# 16_ch_sample-and-hold_card_-_single-side.net
KiCad netlist of a schematic drawn in EAGLE
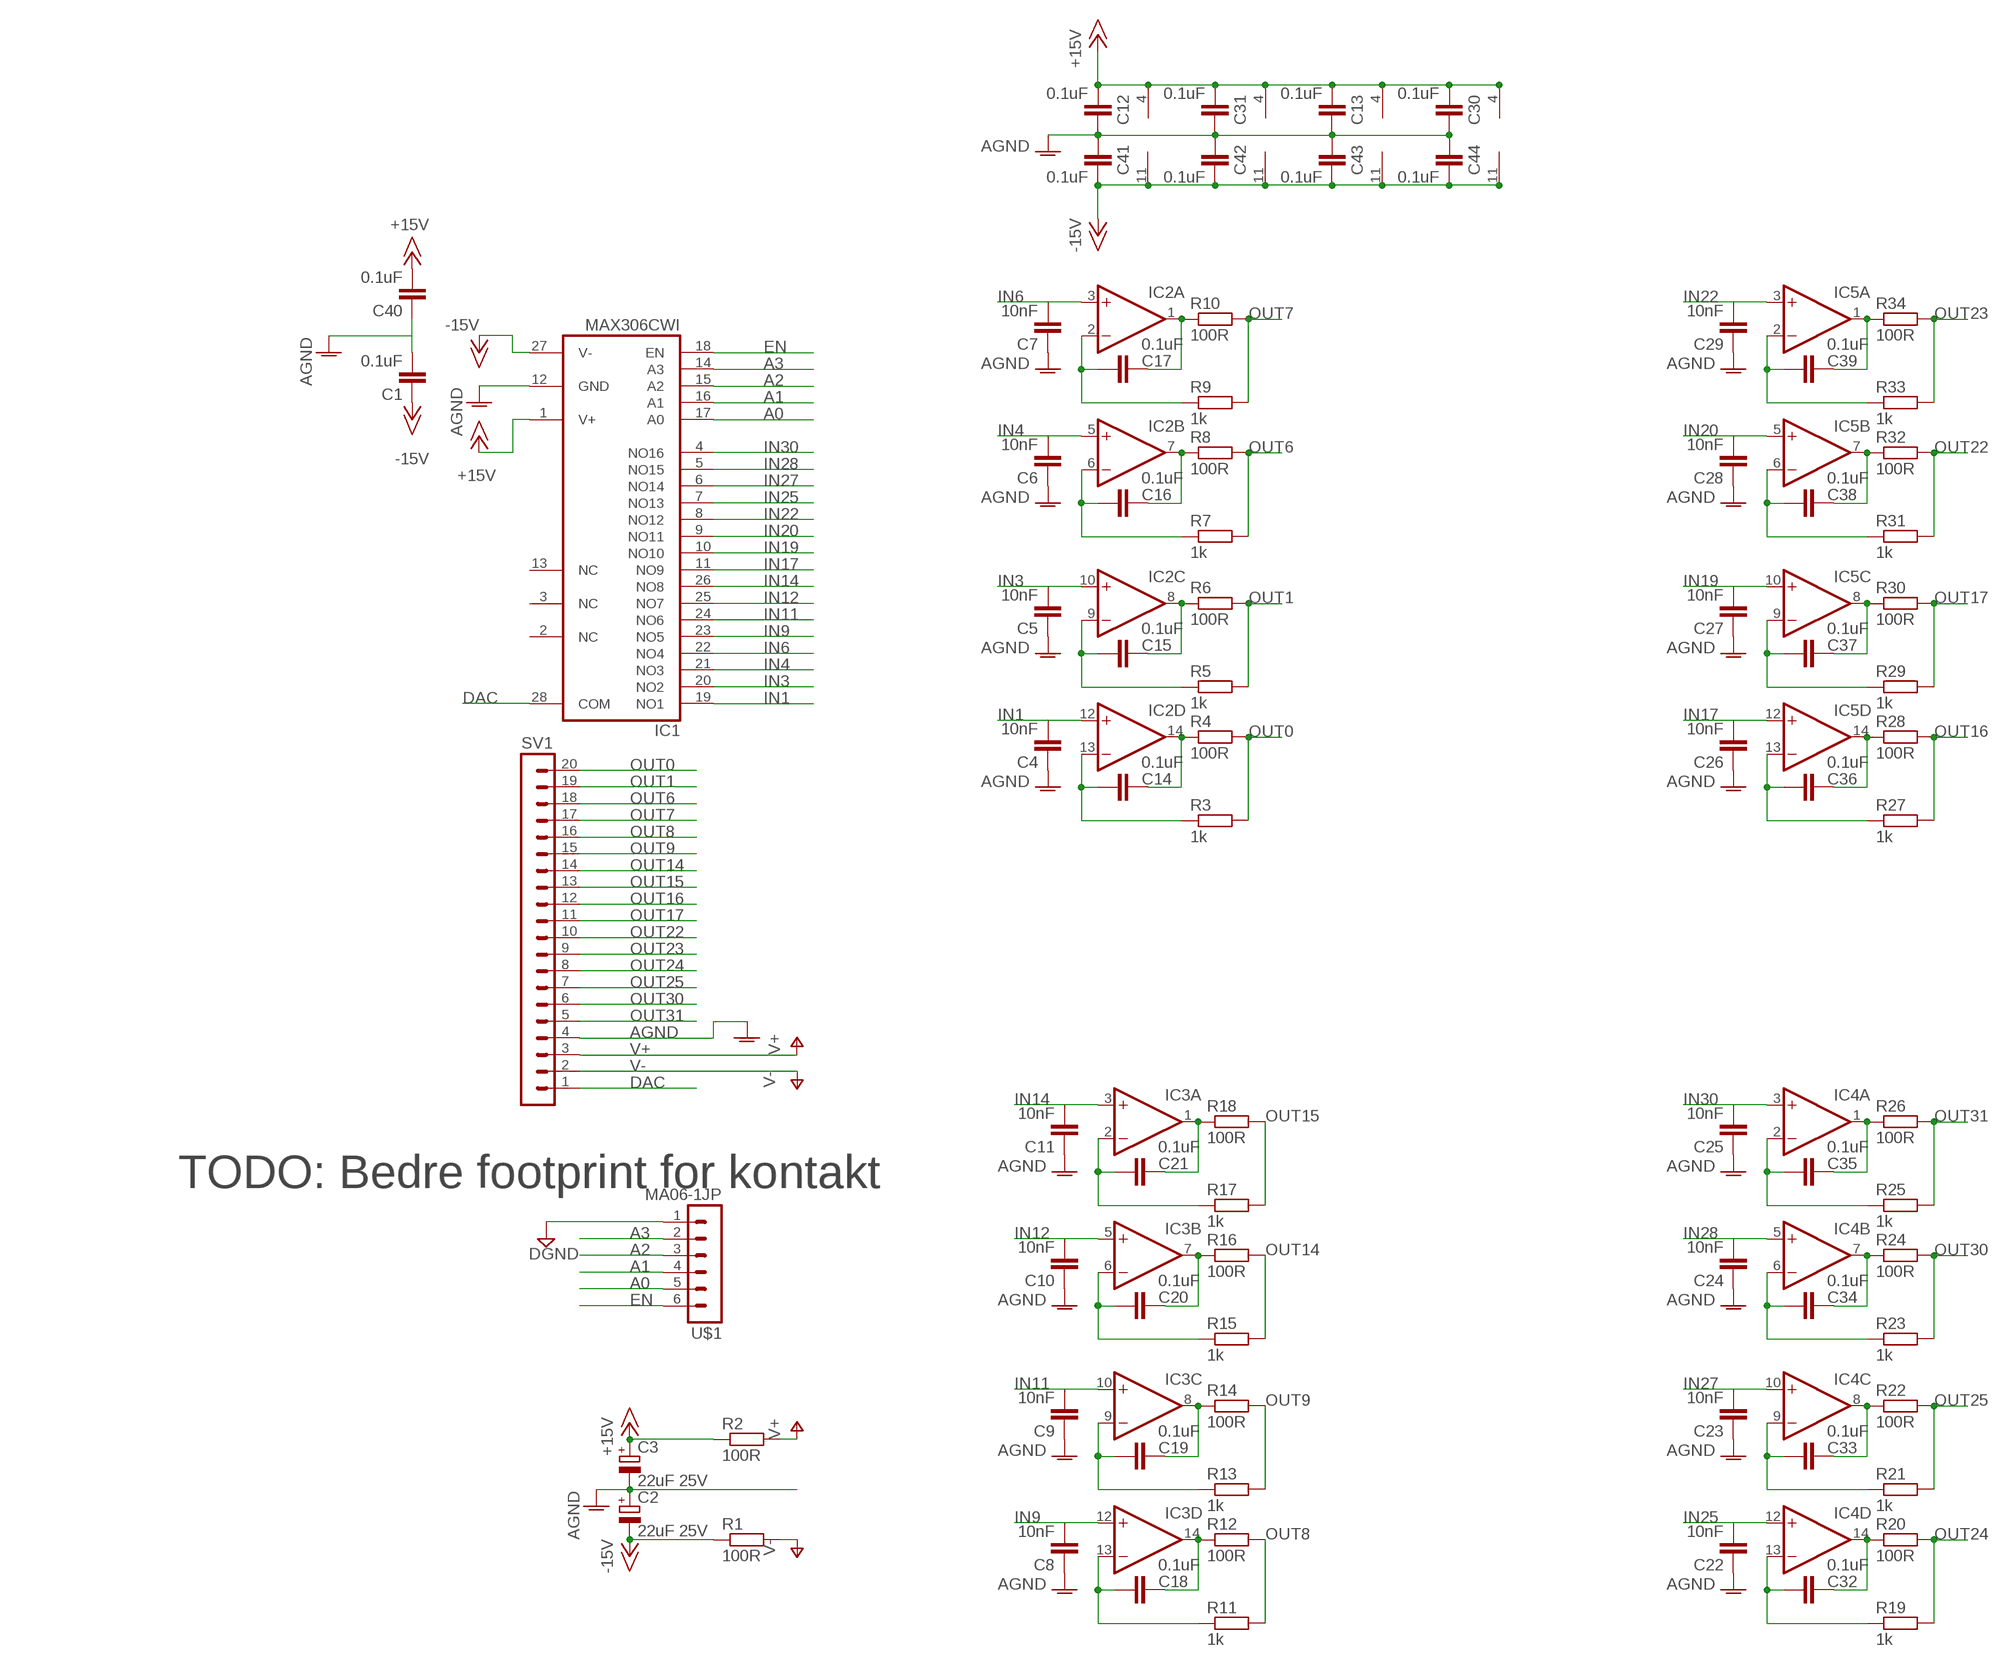
[diagram p0: schematic, sheet 1]

(export (version "E")
  (design (tool "Eeschema 10.0.6"))
  (components
    (comp (ref "C1")
      (value "0.1uF")
      (footprint "eagle-import:C0603")
      (libsource (lib "eagle-import") (part "C-EUC0603"))
    )
    (comp (ref "C2")
      (value "22uF 25V")
      (footprint "eagle-import:E2,5-5")
      (libsource (lib "eagle-import") (part "CPOL-EUE2.5-5"))
    )
    (comp (ref "C3")
      (value "22uF 25V")
      (footprint "eagle-import:E2,5-5")
      (libsource (lib "eagle-import") (part "CPOL-EUE2.5-5"))
    )
    (comp (ref "C4")
      (value "10nF")
      (footprint "eagle-import:C1206")
      (libsource (lib "eagle-import") (part "C-EUC1206"))
    )
    (comp (ref "C5")
      (value "10nF")
      (footprint "eagle-import:C1206")
      (libsource (lib "eagle-import") (part "C-EUC1206"))
    )
    (comp (ref "C6")
      (value "10nF")
      (footprint "eagle-import:C1206")
      (libsource (lib "eagle-import") (part "C-EUC1206"))
    )
    (comp (ref "C7")
      (value "10nF")
      (footprint "eagle-import:C1206")
      (libsource (lib "eagle-import") (part "C-EUC1206"))
    )
    (comp (ref "C8")
      (value "10nF")
      (footprint "eagle-import:C1206")
      (libsource (lib "eagle-import") (part "C-EUC1206"))
    )
    (comp (ref "C9")
      (value "10nF")
      (footprint "eagle-import:C1206")
      (libsource (lib "eagle-import") (part "C-EUC1206"))
    )
    (comp (ref "C10")
      (value "10nF")
      (footprint "eagle-import:C1206")
      (libsource (lib "eagle-import") (part "C-EUC1206"))
    )
    (comp (ref "C11")
      (value "10nF")
      (footprint "eagle-import:C1206")
      (libsource (lib "eagle-import") (part "C-EUC1206"))
    )
    (comp (ref "C12")
      (value "0.1uF")
      (footprint "eagle-import:C0603")
      (libsource (lib "eagle-import") (part "C-EUC0603"))
    )
    (comp (ref "C13")
      (value "0.1uF")
      (footprint "eagle-import:C0603")
      (libsource (lib "eagle-import") (part "C-EUC0603"))
    )
    (comp (ref "C14")
      (value "0.1uF")
      (footprint "eagle-import:C0603")
      (libsource (lib "eagle-import") (part "C-EUC0603"))
    )
    (comp (ref "C15")
      (value "0.1uF")
      (footprint "eagle-import:C0603")
      (libsource (lib "eagle-import") (part "C-EUC0603"))
    )
    (comp (ref "C16")
      (value "0.1uF")
      (footprint "eagle-import:C0603")
      (libsource (lib "eagle-import") (part "C-EUC0603"))
    )
    (comp (ref "C17")
      (value "0.1uF")
      (footprint "eagle-import:C0603")
      (libsource (lib "eagle-import") (part "C-EUC0603"))
    )
    (comp (ref "C18")
      (value "0.1uF")
      (footprint "eagle-import:C0603")
      (libsource (lib "eagle-import") (part "C-EUC0603"))
    )
    (comp (ref "C19")
      (value "0.1uF")
      (footprint "eagle-import:C0603")
      (libsource (lib "eagle-import") (part "C-EUC0603"))
    )
    (comp (ref "C20")
      (value "0.1uF")
      (footprint "eagle-import:C0603")
      (libsource (lib "eagle-import") (part "C-EUC0603"))
    )
    (comp (ref "C21")
      (value "0.1uF")
      (footprint "eagle-import:C0603")
      (libsource (lib "eagle-import") (part "C-EUC0603"))
    )
    (comp (ref "C22")
      (value "10nF")
      (footprint "eagle-import:C1206")
      (libsource (lib "eagle-import") (part "C-EUC1206"))
    )
    (comp (ref "C23")
      (value "10nF")
      (footprint "eagle-import:C1206")
      (libsource (lib "eagle-import") (part "C-EUC1206"))
    )
    (comp (ref "C24")
      (value "10nF")
      (footprint "eagle-import:C1206")
      (libsource (lib "eagle-import") (part "C-EUC1206"))
    )
    (comp (ref "C25")
      (value "10nF")
      (footprint "eagle-import:C1206")
      (libsource (lib "eagle-import") (part "C-EUC1206"))
    )
    (comp (ref "C26")
      (value "10nF")
      (footprint "eagle-import:C1206")
      (libsource (lib "eagle-import") (part "C-EUC1206"))
    )
    (comp (ref "C27")
      (value "10nF")
      (footprint "eagle-import:C1206")
      (libsource (lib "eagle-import") (part "C-EUC1206"))
    )
    (comp (ref "C28")
      (value "10nF")
      (footprint "eagle-import:C1206")
      (libsource (lib "eagle-import") (part "C-EUC1206"))
    )
    (comp (ref "C29")
      (value "10nF")
      (footprint "eagle-import:C1206")
      (libsource (lib "eagle-import") (part "C-EUC1206"))
    )
    (comp (ref "C30")
      (value "0.1uF")
      (footprint "eagle-import:C0603")
      (libsource (lib "eagle-import") (part "C-EUC0603"))
    )
    (comp (ref "C31")
      (value "0.1uF")
      (footprint "eagle-import:C0603")
      (libsource (lib "eagle-import") (part "C-EUC0603"))
    )
    (comp (ref "C32")
      (value "0.1uF")
      (footprint "eagle-import:C0603")
      (libsource (lib "eagle-import") (part "C-EUC0603"))
    )
    (comp (ref "C33")
      (value "0.1uF")
      (footprint "eagle-import:C0603")
      (libsource (lib "eagle-import") (part "C-EUC0603"))
    )
    (comp (ref "C34")
      (value "0.1uF")
      (footprint "eagle-import:C0603")
      (libsource (lib "eagle-import") (part "C-EUC0603"))
    )
    (comp (ref "C35")
      (value "0.1uF")
      (footprint "eagle-import:C0603")
      (libsource (lib "eagle-import") (part "C-EUC0603"))
    )
    (comp (ref "C36")
      (value "0.1uF")
      (footprint "eagle-import:C0603")
      (libsource (lib "eagle-import") (part "C-EUC0603"))
    )
    (comp (ref "C37")
      (value "0.1uF")
      (footprint "eagle-import:C0603")
      (libsource (lib "eagle-import") (part "C-EUC0603"))
    )
    (comp (ref "C38")
      (value "0.1uF")
      (footprint "eagle-import:C0603")
      (libsource (lib "eagle-import") (part "C-EUC0603"))
    )
    (comp (ref "C39")
      (value "0.1uF")
      (footprint "eagle-import:C0603")
      (libsource (lib "eagle-import") (part "C-EUC0603"))
    )
    (comp (ref "C40")
      (value "0.1uF")
      (footprint "eagle-import:C0603")
      (libsource (lib "eagle-import") (part "C-EUC0603"))
    )
    (comp (ref "C41")
      (value "0.1uF")
      (footprint "eagle-import:C0603")
      (libsource (lib "eagle-import") (part "C-EUC0603"))
    )
    (comp (ref "C42")
      (value "0.1uF")
      (footprint "eagle-import:C0603")
      (libsource (lib "eagle-import") (part "C-EUC0603"))
    )
    (comp (ref "C43")
      (value "0.1uF")
      (footprint "eagle-import:C0603")
      (libsource (lib "eagle-import") (part "C-EUC0603"))
    )
    (comp (ref "C44")
      (value "0.1uF")
      (footprint "eagle-import:C0603")
      (libsource (lib "eagle-import") (part "C-EUC0603"))
    )
    (comp (ref "IC1")
      (value "MAX306CWI")
      (footprint "eagle-import:SO28L")
      (fields (field (name "MF") "MAXIM"))
      (libsource (lib "eagle-import") (part "MAX306CWI"))
    )
    (comp (ref "IC2")
      (value "TL074D")
      (footprint "eagle-import:SO14")
      (libsource (lib "eagle-import") (part "TL074D"))
    )
    (comp (ref "IC3")
      (value "TL074D")
      (footprint "eagle-import:SO14")
      (libsource (lib "eagle-import") (part "TL074D"))
    )
    (comp (ref "IC4")
      (value "TL074D")
      (footprint "eagle-import:SO14")
      (libsource (lib "eagle-import") (part "TL074D"))
    )
    (comp (ref "IC5")
      (value "TL074D")
      (footprint "eagle-import:SO14")
      (libsource (lib "eagle-import") (part "TL074D"))
    )
    (comp (ref "R1")
      (value "100R")
      (footprint "eagle-import:0207_7")
      (libsource (lib "eagle-import") (part "R-EU_0207/7"))
    )
    (comp (ref "R2")
      (value "100R")
      (footprint "eagle-import:0207_7")
      (libsource (lib "eagle-import") (part "R-EU_0207/7"))
    )
    (comp (ref "R3")
      (value "1k")
      (footprint "eagle-import:R0603")
      (libsource (lib "eagle-import") (part "R-EU_R0603"))
    )
    (comp (ref "R4")
      (value "100R")
      (footprint "eagle-import:R0603")
      (libsource (lib "eagle-import") (part "R-EU_R0603"))
    )
    (comp (ref "R5")
      (value "1k")
      (footprint "eagle-import:R0603")
      (libsource (lib "eagle-import") (part "R-EU_R0603"))
    )
    (comp (ref "R6")
      (value "100R")
      (footprint "eagle-import:R0603")
      (libsource (lib "eagle-import") (part "R-EU_R0603"))
    )
    (comp (ref "R7")
      (value "1k")
      (footprint "eagle-import:R0603")
      (libsource (lib "eagle-import") (part "R-EU_R0603"))
    )
    (comp (ref "R8")
      (value "100R")
      (footprint "eagle-import:R0603")
      (libsource (lib "eagle-import") (part "R-EU_R0603"))
    )
    (comp (ref "R9")
      (value "1k")
      (footprint "eagle-import:R0603")
      (libsource (lib "eagle-import") (part "R-EU_R0603"))
    )
    (comp (ref "R10")
      (value "100R")
      (footprint "eagle-import:R0603")
      (libsource (lib "eagle-import") (part "R-EU_R0603"))
    )
    (comp (ref "R11")
      (value "1k")
      (footprint "eagle-import:R0603")
      (libsource (lib "eagle-import") (part "R-EU_R0603"))
    )
    (comp (ref "R12")
      (value "100R")
      (footprint "eagle-import:R0603")
      (libsource (lib "eagle-import") (part "R-EU_R0603"))
    )
    (comp (ref "R13")
      (value "1k")
      (footprint "eagle-import:R0603")
      (libsource (lib "eagle-import") (part "R-EU_R0603"))
    )
    (comp (ref "R14")
      (value "100R")
      (footprint "eagle-import:R0603")
      (libsource (lib "eagle-import") (part "R-EU_R0603"))
    )
    (comp (ref "R15")
      (value "1k")
      (footprint "eagle-import:R0603")
      (libsource (lib "eagle-import") (part "R-EU_R0603"))
    )
    (comp (ref "R16")
      (value "100R")
      (footprint "eagle-import:R0603")
      (libsource (lib "eagle-import") (part "R-EU_R0603"))
    )
    (comp (ref "R17")
      (value "1k")
      (footprint "eagle-import:R0603")
      (libsource (lib "eagle-import") (part "R-EU_R0603"))
    )
    (comp (ref "R18")
      (value "100R")
      (footprint "eagle-import:R0603")
      (libsource (lib "eagle-import") (part "R-EU_R0603"))
    )
    (comp (ref "R19")
      (value "1k")
      (footprint "eagle-import:R0603")
      (libsource (lib "eagle-import") (part "R-EU_R0603"))
    )
    (comp (ref "R20")
      (value "100R")
      (footprint "eagle-import:R0603")
      (libsource (lib "eagle-import") (part "R-EU_R0603"))
    )
    (comp (ref "R21")
      (value "1k")
      (footprint "eagle-import:R0603")
      (libsource (lib "eagle-import") (part "R-EU_R0603"))
    )
    (comp (ref "R22")
      (value "100R")
      (footprint "eagle-import:R0603")
      (libsource (lib "eagle-import") (part "R-EU_R0603"))
    )
    (comp (ref "R23")
      (value "1k")
      (footprint "eagle-import:R0603")
      (libsource (lib "eagle-import") (part "R-EU_R0603"))
    )
    (comp (ref "R24")
      (value "100R")
      (footprint "eagle-import:R0603")
      (libsource (lib "eagle-import") (part "R-EU_R0603"))
    )
    (comp (ref "R25")
      (value "1k")
      (footprint "eagle-import:R0603")
      (libsource (lib "eagle-import") (part "R-EU_R0603"))
    )
    (comp (ref "R26")
      (value "100R")
      (footprint "eagle-import:R0603")
      (libsource (lib "eagle-import") (part "R-EU_R0603"))
    )
    (comp (ref "R27")
      (value "1k")
      (footprint "eagle-import:R0603")
      (libsource (lib "eagle-import") (part "R-EU_R0603"))
    )
    (comp (ref "R28")
      (value "100R")
      (footprint "eagle-import:R0603")
      (libsource (lib "eagle-import") (part "R-EU_R0603"))
    )
    (comp (ref "R29")
      (value "1k")
      (footprint "eagle-import:R0603")
      (libsource (lib "eagle-import") (part "R-EU_R0603"))
    )
    (comp (ref "R30")
      (value "100R")
      (footprint "eagle-import:R0603")
      (libsource (lib "eagle-import") (part "R-EU_R0603"))
    )
    (comp (ref "R31")
      (value "1k")
      (footprint "eagle-import:R0603")
      (libsource (lib "eagle-import") (part "R-EU_R0603"))
    )
    (comp (ref "R32")
      (value "100R")
      (footprint "eagle-import:R0603")
      (libsource (lib "eagle-import") (part "R-EU_R0603"))
    )
    (comp (ref "R33")
      (value "1k")
      (footprint "eagle-import:R0603")
      (libsource (lib "eagle-import") (part "R-EU_R0603"))
    )
    (comp (ref "R34")
      (value "100R")
      (footprint "eagle-import:R0603")
      (libsource (lib "eagle-import") (part "R-EU_R0603"))
    )
    (comp (ref "SV1")
      (value "MA20-1JP")
      (footprint "eagle-import:SIP-PIN20-1J")
      (libsource (lib "eagle-import") (part "MA20-1JP"))
    )
    (comp (ref "U$1")
      (value "MA06-1JP")
      (footprint "eagle-import:SIP-PIN06-1J")
      (libsource (lib "eagle-import") (part "MA06-1JP"))
    )
  )
  (nets
    (net (code "1") (name "+15V") (class "Default")
      (node (ref "C12") (pin "1") (pinfunction "1_1") (pintype "passive"))
      (node (ref "C13") (pin "1") (pinfunction "1_1") (pintype "passive"))
      (node (ref "C3") (pin "+") (pinfunction "+_+") (pintype "passive"))
      (node (ref "C30") (pin "1") (pinfunction "1_1") (pintype "passive"))
      (node (ref "C31") (pin "1") (pinfunction "1_1") (pintype "passive"))
      (node (ref "C40") (pin "2") (pinfunction "2_2") (pintype "passive"))
      (node (ref "IC1") (pin "1") (pinfunction "V+_1") (pintype "power_in"))
      (node (ref "IC2") (pin "4") (pinfunction "V+_4") (pintype "power_in"))
      (node (ref "IC3") (pin "4") (pinfunction "V+_4") (pintype "power_in"))
      (node (ref "IC4") (pin "4") (pinfunction "V+_4") (pintype "power_in"))
      (node (ref "IC5") (pin "4") (pinfunction "V+_4") (pintype "power_in"))
      (node (ref "R2") (pin "1") (pinfunction "1_1") (pintype "passive"))
    )
    (net (code "2") (name "-15V") (class "Default")
      (node (ref "C1") (pin "1") (pinfunction "1_1") (pintype "passive"))
      (node (ref "C2") (pin "-") (pinfunction "-_-") (pintype "passive"))
      (node (ref "C41") (pin "2") (pinfunction "2_2") (pintype "passive"))
      (node (ref "C42") (pin "2") (pinfunction "2_2") (pintype "passive"))
      (node (ref "C43") (pin "2") (pinfunction "2_2") (pintype "passive"))
      (node (ref "C44") (pin "2") (pinfunction "2_2") (pintype "passive"))
      (node (ref "IC1") (pin "27") (pinfunction "V-_27") (pintype "power_in"))
      (node (ref "IC2") (pin "11") (pinfunction "V-_11") (pintype "power_in"))
      (node (ref "IC3") (pin "11") (pinfunction "V-_11") (pintype "power_in"))
      (node (ref "IC4") (pin "11") (pinfunction "V-_11") (pintype "power_in"))
      (node (ref "IC5") (pin "11") (pinfunction "V-_11") (pintype "power_in"))
      (node (ref "R1") (pin "1") (pinfunction "1_1") (pintype "passive"))
    )
    (net (code "3") (name "/A0") (class "Default")
      (node (ref "IC1") (pin "17") (pinfunction "A0_17") (pintype "input"))
      (node (ref "U$1") (pin "5") (pinfunction "5_5") (pintype "passive"))
    )
    (net (code "4") (name "/A1") (class "Default")
      (node (ref "IC1") (pin "16") (pinfunction "A1_16") (pintype "input"))
      (node (ref "U$1") (pin "4") (pinfunction "4_4") (pintype "passive"))
    )
    (net (code "5") (name "/A2") (class "Default")
      (node (ref "IC1") (pin "15") (pinfunction "A2_15") (pintype "input"))
      (node (ref "U$1") (pin "3") (pinfunction "3_3") (pintype "passive"))
    )
    (net (code "6") (name "/A3") (class "Default")
      (node (ref "IC1") (pin "14") (pinfunction "A3_14") (pintype "input"))
      (node (ref "U$1") (pin "2") (pinfunction "2_2") (pintype "passive"))
    )
    (net (code "7") (name "/DAC") (class "Default")
      (node (ref "IC1") (pin "28") (pinfunction "COM_28") (pintype "passive"))
      (node (ref "SV1") (pin "1") (pinfunction "1_1") (pintype "passive"))
    )
    (net (code "8") (name "/EN") (class "Default")
      (node (ref "IC1") (pin "18") (pinfunction "EN_18") (pintype "input"))
      (node (ref "U$1") (pin "6") (pinfunction "6_6") (pintype "passive"))
    )
    (net (code "9") (name "/IN1") (class "Default")
      (node (ref "C4") (pin "2") (pinfunction "2_2") (pintype "passive"))
      (node (ref "IC1") (pin "19") (pinfunction "NO1_19") (pintype "passive"))
      (node (ref "IC2") (pin "12") (pinfunction "+IN_12") (pintype "input"))
    )
    (net (code "10") (name "/IN3") (class "Default")
      (node (ref "C5") (pin "2") (pinfunction "2_2") (pintype "passive"))
      (node (ref "IC1") (pin "20") (pinfunction "NO2_20") (pintype "passive"))
      (node (ref "IC2") (pin "10") (pinfunction "+IN_10") (pintype "input"))
    )
    (net (code "11") (name "/IN4") (class "Default")
      (node (ref "C6") (pin "2") (pinfunction "2_2") (pintype "passive"))
      (node (ref "IC1") (pin "21") (pinfunction "NO3_21") (pintype "passive"))
      (node (ref "IC2") (pin "5") (pinfunction "+IN_5") (pintype "input"))
    )
    (net (code "12") (name "/IN6") (class "Default")
      (node (ref "C7") (pin "2") (pinfunction "2_2") (pintype "passive"))
      (node (ref "IC1") (pin "22") (pinfunction "NO4_22") (pintype "passive"))
      (node (ref "IC2") (pin "3") (pinfunction "+IN_3") (pintype "input"))
    )
    (net (code "13") (name "/IN9") (class "Default")
      (node (ref "C8") (pin "2") (pinfunction "2_2") (pintype "passive"))
      (node (ref "IC1") (pin "23") (pinfunction "NO5_23") (pintype "passive"))
      (node (ref "IC3") (pin "12") (pinfunction "+IN_12") (pintype "input"))
    )
    (net (code "14") (name "/IN11") (class "Default")
      (node (ref "C9") (pin "2") (pinfunction "2_2") (pintype "passive"))
      (node (ref "IC1") (pin "24") (pinfunction "NO6_24") (pintype "passive"))
      (node (ref "IC3") (pin "10") (pinfunction "+IN_10") (pintype "input"))
    )
    (net (code "15") (name "/IN12") (class "Default")
      (node (ref "C10") (pin "2") (pinfunction "2_2") (pintype "passive"))
      (node (ref "IC1") (pin "25") (pinfunction "NO7_25") (pintype "passive"))
      (node (ref "IC3") (pin "5") (pinfunction "+IN_5") (pintype "input"))
    )
    (net (code "16") (name "/IN14") (class "Default")
      (node (ref "C11") (pin "2") (pinfunction "2_2") (pintype "passive"))
      (node (ref "IC1") (pin "26") (pinfunction "NO8_26") (pintype "passive"))
      (node (ref "IC3") (pin "3") (pinfunction "+IN_3") (pintype "input"))
    )
    (net (code "17") (name "/IN17") (class "Default")
      (node (ref "C26") (pin "2") (pinfunction "2_2") (pintype "passive"))
      (node (ref "IC1") (pin "11") (pinfunction "NO9_11") (pintype "passive"))
      (node (ref "IC5") (pin "12") (pinfunction "+IN_12") (pintype "input"))
    )
    (net (code "18") (name "/IN19") (class "Default")
      (node (ref "C27") (pin "2") (pinfunction "2_2") (pintype "passive"))
      (node (ref "IC1") (pin "10") (pinfunction "NO10_10") (pintype "passive"))
      (node (ref "IC5") (pin "10") (pinfunction "+IN_10") (pintype "input"))
    )
    (net (code "19") (name "/IN20") (class "Default")
      (node (ref "C28") (pin "2") (pinfunction "2_2") (pintype "passive"))
      (node (ref "IC1") (pin "9") (pinfunction "NO11_9") (pintype "passive"))
      (node (ref "IC5") (pin "5") (pinfunction "+IN_5") (pintype "input"))
    )
    (net (code "20") (name "/IN22") (class "Default")
      (node (ref "C29") (pin "2") (pinfunction "2_2") (pintype "passive"))
      (node (ref "IC1") (pin "8") (pinfunction "NO12_8") (pintype "passive"))
      (node (ref "IC5") (pin "3") (pinfunction "+IN_3") (pintype "input"))
    )
    (net (code "21") (name "/IN25") (class "Default")
      (node (ref "C22") (pin "2") (pinfunction "2_2") (pintype "passive"))
      (node (ref "IC1") (pin "7") (pinfunction "NO13_7") (pintype "passive"))
      (node (ref "IC4") (pin "12") (pinfunction "+IN_12") (pintype "input"))
    )
    (net (code "22") (name "/IN27") (class "Default")
      (node (ref "C23") (pin "2") (pinfunction "2_2") (pintype "passive"))
      (node (ref "IC1") (pin "6") (pinfunction "NO14_6") (pintype "passive"))
      (node (ref "IC4") (pin "10") (pinfunction "+IN_10") (pintype "input"))
    )
    (net (code "23") (name "/IN28") (class "Default")
      (node (ref "C24") (pin "2") (pinfunction "2_2") (pintype "passive"))
      (node (ref "IC1") (pin "5") (pinfunction "NO15_5") (pintype "passive"))
      (node (ref "IC4") (pin "5") (pinfunction "+IN_5") (pintype "input"))
    )
    (net (code "24") (name "/IN30") (class "Default")
      (node (ref "C25") (pin "2") (pinfunction "2_2") (pintype "passive"))
      (node (ref "IC1") (pin "4") (pinfunction "NO16_4") (pintype "passive"))
      (node (ref "IC4") (pin "3") (pinfunction "+IN_3") (pintype "input"))
    )
    (net (code "25") (name "/OUT0") (class "Default")
      (node (ref "R3") (pin "2") (pinfunction "2_2") (pintype "passive"))
      (node (ref "R4") (pin "2") (pinfunction "2_2") (pintype "passive"))
      (node (ref "SV1") (pin "20") (pinfunction "20_20") (pintype "passive"))
    )
    (net (code "26") (name "/OUT1") (class "Default")
      (node (ref "R5") (pin "2") (pinfunction "2_2") (pintype "passive"))
      (node (ref "R6") (pin "2") (pinfunction "2_2") (pintype "passive"))
      (node (ref "SV1") (pin "19") (pinfunction "19_19") (pintype "passive"))
    )
    (net (code "27") (name "/OUT6") (class "Default")
      (node (ref "R7") (pin "2") (pinfunction "2_2") (pintype "passive"))
      (node (ref "R8") (pin "2") (pinfunction "2_2") (pintype "passive"))
      (node (ref "SV1") (pin "18") (pinfunction "18_18") (pintype "passive"))
    )
    (net (code "28") (name "/OUT7") (class "Default")
      (node (ref "R10") (pin "2") (pinfunction "2_2") (pintype "passive"))
      (node (ref "R9") (pin "2") (pinfunction "2_2") (pintype "passive"))
      (node (ref "SV1") (pin "17") (pinfunction "17_17") (pintype "passive"))
    )
    (net (code "29") (name "/OUT8") (class "Default")
      (node (ref "R11") (pin "2") (pinfunction "2_2") (pintype "passive"))
      (node (ref "R12") (pin "2") (pinfunction "2_2") (pintype "passive"))
      (node (ref "SV1") (pin "16") (pinfunction "16_16") (pintype "passive"))
    )
    (net (code "30") (name "/OUT9") (class "Default")
      (node (ref "R13") (pin "2") (pinfunction "2_2") (pintype "passive"))
      (node (ref "R14") (pin "2") (pinfunction "2_2") (pintype "passive"))
      (node (ref "SV1") (pin "15") (pinfunction "15_15") (pintype "passive"))
    )
    (net (code "31") (name "/OUT14") (class "Default")
      (node (ref "R15") (pin "2") (pinfunction "2_2") (pintype "passive"))
      (node (ref "R16") (pin "2") (pinfunction "2_2") (pintype "passive"))
      (node (ref "SV1") (pin "14") (pinfunction "14_14") (pintype "passive"))
    )
    (net (code "32") (name "/OUT15") (class "Default")
      (node (ref "R17") (pin "2") (pinfunction "2_2") (pintype "passive"))
      (node (ref "R18") (pin "2") (pinfunction "2_2") (pintype "passive"))
      (node (ref "SV1") (pin "13") (pinfunction "13_13") (pintype "passive"))
    )
    (net (code "33") (name "/OUT16") (class "Default")
      (node (ref "R27") (pin "2") (pinfunction "2_2") (pintype "passive"))
      (node (ref "R28") (pin "2") (pinfunction "2_2") (pintype "passive"))
      (node (ref "SV1") (pin "12") (pinfunction "12_12") (pintype "passive"))
    )
    (net (code "34") (name "/OUT17") (class "Default")
      (node (ref "R29") (pin "2") (pinfunction "2_2") (pintype "passive"))
      (node (ref "R30") (pin "2") (pinfunction "2_2") (pintype "passive"))
      (node (ref "SV1") (pin "11") (pinfunction "11_11") (pintype "passive"))
    )
    (net (code "35") (name "/OUT22") (class "Default")
      (node (ref "R31") (pin "2") (pinfunction "2_2") (pintype "passive"))
      (node (ref "R32") (pin "2") (pinfunction "2_2") (pintype "passive"))
      (node (ref "SV1") (pin "10") (pinfunction "10_10") (pintype "passive"))
    )
    (net (code "36") (name "/OUT23") (class "Default")
      (node (ref "R33") (pin "2") (pinfunction "2_2") (pintype "passive"))
      (node (ref "R34") (pin "2") (pinfunction "2_2") (pintype "passive"))
      (node (ref "SV1") (pin "9") (pinfunction "9_9") (pintype "passive"))
    )
    (net (code "37") (name "/OUT24") (class "Default")
      (node (ref "R19") (pin "2") (pinfunction "2_2") (pintype "passive"))
      (node (ref "R20") (pin "2") (pinfunction "2_2") (pintype "passive"))
      (node (ref "SV1") (pin "8") (pinfunction "8_8") (pintype "passive"))
    )
    (net (code "38") (name "/OUT25") (class "Default")
      (node (ref "R21") (pin "2") (pinfunction "2_2") (pintype "passive"))
      (node (ref "R22") (pin "2") (pinfunction "2_2") (pintype "passive"))
      (node (ref "SV1") (pin "7") (pinfunction "7_7") (pintype "passive"))
    )
    (net (code "39") (name "/OUT30") (class "Default")
      (node (ref "R23") (pin "2") (pinfunction "2_2") (pintype "passive"))
      (node (ref "R24") (pin "2") (pinfunction "2_2") (pintype "passive"))
      (node (ref "SV1") (pin "6") (pinfunction "6_6") (pintype "passive"))
    )
    (net (code "40") (name "/OUT31") (class "Default")
      (node (ref "R25") (pin "2") (pinfunction "2_2") (pintype "passive"))
      (node (ref "R26") (pin "2") (pinfunction "2_2") (pintype "passive"))
      (node (ref "SV1") (pin "5") (pinfunction "5_5") (pintype "passive"))
    )
    (net (code "41") (name "AGND") (class "Default")
      (node (ref "C1") (pin "2") (pinfunction "2_2") (pintype "passive"))
      (node (ref "C10") (pin "1") (pinfunction "1_1") (pintype "passive"))
      (node (ref "C11") (pin "1") (pinfunction "1_1") (pintype "passive"))
      (node (ref "C12") (pin "2") (pinfunction "2_2") (pintype "passive"))
      (node (ref "C13") (pin "2") (pinfunction "2_2") (pintype "passive"))
      (node (ref "C2") (pin "+") (pinfunction "+_+") (pintype "passive"))
      (node (ref "C22") (pin "1") (pinfunction "1_1") (pintype "passive"))
      (node (ref "C23") (pin "1") (pinfunction "1_1") (pintype "passive"))
      (node (ref "C24") (pin "1") (pinfunction "1_1") (pintype "passive"))
      (node (ref "C25") (pin "1") (pinfunction "1_1") (pintype "passive"))
      (node (ref "C26") (pin "1") (pinfunction "1_1") (pintype "passive"))
      (node (ref "C27") (pin "1") (pinfunction "1_1") (pintype "passive"))
      (node (ref "C28") (pin "1") (pinfunction "1_1") (pintype "passive"))
      (node (ref "C29") (pin "1") (pinfunction "1_1") (pintype "passive"))
      (node (ref "C3") (pin "-") (pinfunction "-_-") (pintype "passive"))
      (node (ref "C30") (pin "2") (pinfunction "2_2") (pintype "passive"))
      (node (ref "C31") (pin "2") (pinfunction "2_2") (pintype "passive"))
      (node (ref "C4") (pin "1") (pinfunction "1_1") (pintype "passive"))
      (node (ref "C40") (pin "1") (pinfunction "1_1") (pintype "passive"))
      (node (ref "C41") (pin "1") (pinfunction "1_1") (pintype "passive"))
      (node (ref "C42") (pin "1") (pinfunction "1_1") (pintype "passive"))
      (node (ref "C43") (pin "1") (pinfunction "1_1") (pintype "passive"))
      (node (ref "C44") (pin "1") (pinfunction "1_1") (pintype "passive"))
      (node (ref "C5") (pin "1") (pinfunction "1_1") (pintype "passive"))
      (node (ref "C6") (pin "1") (pinfunction "1_1") (pintype "passive"))
      (node (ref "C7") (pin "1") (pinfunction "1_1") (pintype "passive"))
      (node (ref "C8") (pin "1") (pinfunction "1_1") (pintype "passive"))
      (node (ref "C9") (pin "1") (pinfunction "1_1") (pintype "passive"))
      (node (ref "IC1") (pin "12") (pinfunction "GND_12") (pintype "power_in"))
      (node (ref "SV1") (pin "4") (pinfunction "4_4") (pintype "passive"))
    )
    (net (code "42") (name "DGND") (class "Default")
      (node (ref "U$1") (pin "1") (pinfunction "1_1") (pintype "passive"))
    )
    (net (code "43") (name "Net-(IC2A--IN)") (class "Default")
      (node (ref "C17") (pin "2") (pinfunction "2_2") (pintype "passive"))
      (node (ref "IC2") (pin "2") (pinfunction "-IN_2") (pintype "input"))
      (node (ref "R9") (pin "1") (pinfunction "1_1") (pintype "passive"))
    )
    (net (code "44") (name "Net-(IC2A-OUT)") (class "Default")
      (node (ref "C17") (pin "1") (pinfunction "1_1") (pintype "passive"))
      (node (ref "IC2") (pin "1") (pinfunction "OUT_1") (pintype "output"))
      (node (ref "R10") (pin "1") (pinfunction "1_1") (pintype "passive"))
    )
    (net (code "45") (name "Net-(IC2B--IN)") (class "Default")
      (node (ref "C16") (pin "2") (pinfunction "2_2") (pintype "passive"))
      (node (ref "IC2") (pin "6") (pinfunction "-IN_6") (pintype "input"))
      (node (ref "R7") (pin "1") (pinfunction "1_1") (pintype "passive"))
    )
    (net (code "46") (name "Net-(IC2B-OUT)") (class "Default")
      (node (ref "C16") (pin "1") (pinfunction "1_1") (pintype "passive"))
      (node (ref "IC2") (pin "7") (pinfunction "OUT_7") (pintype "output"))
      (node (ref "R8") (pin "1") (pinfunction "1_1") (pintype "passive"))
    )
    (net (code "47") (name "Net-(IC2C--IN)") (class "Default")
      (node (ref "C15") (pin "2") (pinfunction "2_2") (pintype "passive"))
      (node (ref "IC2") (pin "9") (pinfunction "-IN_9") (pintype "input"))
      (node (ref "R5") (pin "1") (pinfunction "1_1") (pintype "passive"))
    )
    (net (code "48") (name "Net-(IC2C-OUT)") (class "Default")
      (node (ref "C15") (pin "1") (pinfunction "1_1") (pintype "passive"))
      (node (ref "IC2") (pin "8") (pinfunction "OUT_8") (pintype "output"))
      (node (ref "R6") (pin "1") (pinfunction "1_1") (pintype "passive"))
    )
    (net (code "49") (name "Net-(IC2D--IN)") (class "Default")
      (node (ref "C14") (pin "2") (pinfunction "2_2") (pintype "passive"))
      (node (ref "IC2") (pin "13") (pinfunction "-IN_13") (pintype "input"))
      (node (ref "R3") (pin "1") (pinfunction "1_1") (pintype "passive"))
    )
    (net (code "50") (name "Net-(IC2D-OUT)") (class "Default")
      (node (ref "C14") (pin "1") (pinfunction "1_1") (pintype "passive"))
      (node (ref "IC2") (pin "14") (pinfunction "OUT_14") (pintype "output"))
      (node (ref "R4") (pin "1") (pinfunction "1_1") (pintype "passive"))
    )
    (net (code "51") (name "Net-(IC3A--IN)") (class "Default")
      (node (ref "C21") (pin "2") (pinfunction "2_2") (pintype "passive"))
      (node (ref "IC3") (pin "2") (pinfunction "-IN_2") (pintype "input"))
      (node (ref "R17") (pin "1") (pinfunction "1_1") (pintype "passive"))
    )
    (net (code "52") (name "Net-(IC3A-OUT)") (class "Default")
      (node (ref "C21") (pin "1") (pinfunction "1_1") (pintype "passive"))
      (node (ref "IC3") (pin "1") (pinfunction "OUT_1") (pintype "output"))
      (node (ref "R18") (pin "1") (pinfunction "1_1") (pintype "passive"))
    )
    (net (code "53") (name "Net-(IC3B--IN)") (class "Default")
      (node (ref "C20") (pin "2") (pinfunction "2_2") (pintype "passive"))
      (node (ref "IC3") (pin "6") (pinfunction "-IN_6") (pintype "input"))
      (node (ref "R15") (pin "1") (pinfunction "1_1") (pintype "passive"))
    )
    (net (code "54") (name "Net-(IC3B-OUT)") (class "Default")
      (node (ref "C20") (pin "1") (pinfunction "1_1") (pintype "passive"))
      (node (ref "IC3") (pin "7") (pinfunction "OUT_7") (pintype "output"))
      (node (ref "R16") (pin "1") (pinfunction "1_1") (pintype "passive"))
    )
    (net (code "55") (name "Net-(IC3C--IN)") (class "Default")
      (node (ref "C19") (pin "2") (pinfunction "2_2") (pintype "passive"))
      (node (ref "IC3") (pin "9") (pinfunction "-IN_9") (pintype "input"))
      (node (ref "R13") (pin "1") (pinfunction "1_1") (pintype "passive"))
    )
    (net (code "56") (name "Net-(IC3C-OUT)") (class "Default")
      (node (ref "C19") (pin "1") (pinfunction "1_1") (pintype "passive"))
      (node (ref "IC3") (pin "8") (pinfunction "OUT_8") (pintype "output"))
      (node (ref "R14") (pin "1") (pinfunction "1_1") (pintype "passive"))
    )
    (net (code "57") (name "Net-(IC3D--IN)") (class "Default")
      (node (ref "C18") (pin "2") (pinfunction "2_2") (pintype "passive"))
      (node (ref "IC3") (pin "13") (pinfunction "-IN_13") (pintype "input"))
      (node (ref "R11") (pin "1") (pinfunction "1_1") (pintype "passive"))
    )
    (net (code "58") (name "Net-(IC3D-OUT)") (class "Default")
      (node (ref "C18") (pin "1") (pinfunction "1_1") (pintype "passive"))
      (node (ref "IC3") (pin "14") (pinfunction "OUT_14") (pintype "output"))
      (node (ref "R12") (pin "1") (pinfunction "1_1") (pintype "passive"))
    )
    (net (code "59") (name "Net-(IC4A--IN)") (class "Default")
      (node (ref "C35") (pin "2") (pinfunction "2_2") (pintype "passive"))
      (node (ref "IC4") (pin "2") (pinfunction "-IN_2") (pintype "input"))
      (node (ref "R25") (pin "1") (pinfunction "1_1") (pintype "passive"))
    )
    (net (code "60") (name "Net-(IC4A-OUT)") (class "Default")
      (node (ref "C35") (pin "1") (pinfunction "1_1") (pintype "passive"))
      (node (ref "IC4") (pin "1") (pinfunction "OUT_1") (pintype "output"))
      (node (ref "R26") (pin "1") (pinfunction "1_1") (pintype "passive"))
    )
    (net (code "61") (name "Net-(IC4B--IN)") (class "Default")
      (node (ref "C34") (pin "2") (pinfunction "2_2") (pintype "passive"))
      (node (ref "IC4") (pin "6") (pinfunction "-IN_6") (pintype "input"))
      (node (ref "R23") (pin "1") (pinfunction "1_1") (pintype "passive"))
    )
    (net (code "62") (name "Net-(IC4B-OUT)") (class "Default")
      (node (ref "C34") (pin "1") (pinfunction "1_1") (pintype "passive"))
      (node (ref "IC4") (pin "7") (pinfunction "OUT_7") (pintype "output"))
      (node (ref "R24") (pin "1") (pinfunction "1_1") (pintype "passive"))
    )
    (net (code "63") (name "Net-(IC4C--IN)") (class "Default")
      (node (ref "C33") (pin "2") (pinfunction "2_2") (pintype "passive"))
      (node (ref "IC4") (pin "9") (pinfunction "-IN_9") (pintype "input"))
      (node (ref "R21") (pin "1") (pinfunction "1_1") (pintype "passive"))
    )
    (net (code "64") (name "Net-(IC4C-OUT)") (class "Default")
      (node (ref "C33") (pin "1") (pinfunction "1_1") (pintype "passive"))
      (node (ref "IC4") (pin "8") (pinfunction "OUT_8") (pintype "output"))
      (node (ref "R22") (pin "1") (pinfunction "1_1") (pintype "passive"))
    )
    (net (code "65") (name "Net-(IC4D--IN)") (class "Default")
      (node (ref "C32") (pin "2") (pinfunction "2_2") (pintype "passive"))
      (node (ref "IC4") (pin "13") (pinfunction "-IN_13") (pintype "input"))
      (node (ref "R19") (pin "1") (pinfunction "1_1") (pintype "passive"))
    )
    (net (code "66") (name "Net-(IC4D-OUT)") (class "Default")
      (node (ref "C32") (pin "1") (pinfunction "1_1") (pintype "passive"))
      (node (ref "IC4") (pin "14") (pinfunction "OUT_14") (pintype "output"))
      (node (ref "R20") (pin "1") (pinfunction "1_1") (pintype "passive"))
    )
    (net (code "67") (name "Net-(IC5A--IN)") (class "Default")
      (node (ref "C39") (pin "2") (pinfunction "2_2") (pintype "passive"))
      (node (ref "IC5") (pin "2") (pinfunction "-IN_2") (pintype "input"))
      (node (ref "R33") (pin "1") (pinfunction "1_1") (pintype "passive"))
    )
    (net (code "68") (name "Net-(IC5A-OUT)") (class "Default")
      (node (ref "C39") (pin "1") (pinfunction "1_1") (pintype "passive"))
      (node (ref "IC5") (pin "1") (pinfunction "OUT_1") (pintype "output"))
      (node (ref "R34") (pin "1") (pinfunction "1_1") (pintype "passive"))
    )
    (net (code "69") (name "Net-(IC5B--IN)") (class "Default")
      (node (ref "C38") (pin "2") (pinfunction "2_2") (pintype "passive"))
      (node (ref "IC5") (pin "6") (pinfunction "-IN_6") (pintype "input"))
      (node (ref "R31") (pin "1") (pinfunction "1_1") (pintype "passive"))
    )
    (net (code "70") (name "Net-(IC5B-OUT)") (class "Default")
      (node (ref "C38") (pin "1") (pinfunction "1_1") (pintype "passive"))
      (node (ref "IC5") (pin "7") (pinfunction "OUT_7") (pintype "output"))
      (node (ref "R32") (pin "1") (pinfunction "1_1") (pintype "passive"))
    )
    (net (code "71") (name "Net-(IC5C--IN)") (class "Default")
      (node (ref "C37") (pin "2") (pinfunction "2_2") (pintype "passive"))
      (node (ref "IC5") (pin "9") (pinfunction "-IN_9") (pintype "input"))
      (node (ref "R29") (pin "1") (pinfunction "1_1") (pintype "passive"))
    )
    (net (code "72") (name "Net-(IC5C-OUT)") (class "Default")
      (node (ref "C37") (pin "1") (pinfunction "1_1") (pintype "passive"))
      (node (ref "IC5") (pin "8") (pinfunction "OUT_8") (pintype "output"))
      (node (ref "R30") (pin "1") (pinfunction "1_1") (pintype "passive"))
    )
    (net (code "73") (name "Net-(IC5D--IN)") (class "Default")
      (node (ref "C36") (pin "2") (pinfunction "2_2") (pintype "passive"))
      (node (ref "IC5") (pin "13") (pinfunction "-IN_13") (pintype "input"))
      (node (ref "R27") (pin "1") (pinfunction "1_1") (pintype "passive"))
    )
    (net (code "74") (name "Net-(IC5D-OUT)") (class "Default")
      (node (ref "C36") (pin "1") (pinfunction "1_1") (pintype "passive"))
      (node (ref "IC5") (pin "14") (pinfunction "OUT_14") (pintype "output"))
      (node (ref "R28") (pin "1") (pinfunction "1_1") (pintype "passive"))
    )
    (net (code "75") (name "V+") (class "Default")
      (node (ref "R2") (pin "2") (pinfunction "2_2") (pintype "passive"))
      (node (ref "SV1") (pin "3") (pinfunction "3_3") (pintype "passive"))
    )
    (net (code "76") (name "V-") (class "Default")
      (node (ref "R1") (pin "2") (pinfunction "2_2") (pintype "passive"))
      (node (ref "SV1") (pin "2") (pinfunction "2_2") (pintype "passive"))
    )
    (net (code "77") (name "unconnected-(IC1-NC-Pad2)") (class "Default")
      (node (ref "IC1") (pin "2") (pinfunction "NC_2") (pintype "no_connect"))
    )
    (net (code "78") (name "unconnected-(IC1-NC-Pad3)") (class "Default")
      (node (ref "IC1") (pin "3") (pinfunction "NC_3") (pintype "no_connect"))
    )
    (net (code "79") (name "unconnected-(IC1-NC-Pad13)") (class "Default")
      (node (ref "IC1") (pin "13") (pinfunction "NC_13") (pintype "no_connect"))
    )
  )
)
